# TOP.net
KiCad netlist of a schematic drawn in Altium Designer
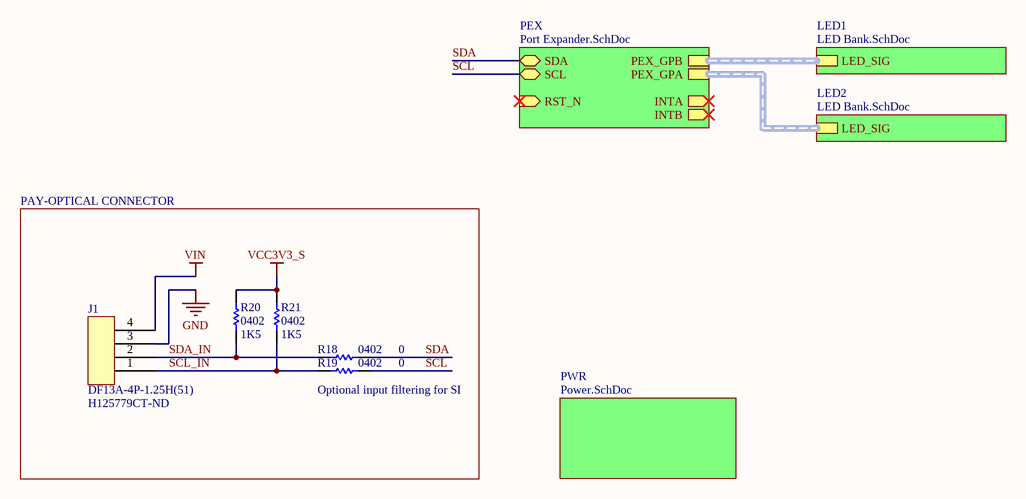
[diagram p0: TOP.SchDoc]

(export (version "E")
  (design (tool "Eeschema 10.0.6"))
  (components
    (comp (ref "J1")
      (value "DF13A-4P-1.25H(51)")
      (footprint "DF13A-4P-1.25H(51)")
      (description "4 pos DF13 right angle surface mount connector")
      (fields (field (name "SUPPLIER PART NUMBER 1") "H125779CT-ND"))
      (libsource (lib "heron-general") (part "DF13A-4P-1.25H(51)"))
    )
    (comp (ref "R18")
      (value "0402")
      (footprint "RES0402R")
      (description "0402 resistor")
      (fields
        (field (name "ALTIUM_VALUE") "0")
        (field (name "MANUFACTURER") "Panasonic")
        (field (name "MANUFACTURER PART NUMBER") "ERJ-2GE0R00X")
      )
      (libsource (lib "heron-general") (part "RES0402"))
    )
    (comp (ref "R19")
      (value "0402")
      (footprint "RES0402R")
      (description "0402 resistor")
      (fields
        (field (name "ALTIUM_VALUE") "0")
        (field (name "MANUFACTURER") "Panasonic")
        (field (name "MANUFACTURER PART NUMBER") "ERJ-2GE0R00X")
      )
      (libsource (lib "heron-general") (part "RES0402"))
    )
    (comp (ref "R20")
      (value "0402")
      (footprint "RES0402R")
      (description "0402 resistor")
      (fields (field (name "ALTIUM_VALUE") "1K5"))
      (libsource (lib "heron-general") (part "RES0402"))
    )
    (comp (ref "R21")
      (value "0402")
      (footprint "RES0402R")
      (description "0402 resistor")
      (fields (field (name "ALTIUM_VALUE") "1K5"))
      (libsource (lib "heron-general") (part "RES0402"))
    )
  )
  (nets
    (net (code "6") (name "/SCL") (class "Default")
      (node (ref "R19") (pin "2") (pinfunction "2_2") (pintype "passive"))
    )
    (net (code "7") (name "/SCL_IN") (class "Default")
      (node (ref "J1") (pin "1") (pintype "passive"))
      (node (ref "R19") (pin "1") (pinfunction "1_1") (pintype "passive"))
      (node (ref "R21") (pin "1") (pinfunction "1_1") (pintype "passive"))
    )
    (net (code "8") (name "/SDA") (class "Default")
      (node (ref "R18") (pin "2") (pinfunction "2_2") (pintype "passive"))
    )
    (net (code "9") (name "/SDA_IN") (class "Default")
      (node (ref "J1") (pin "2") (pintype "passive"))
      (node (ref "R18") (pin "1") (pinfunction "1_1") (pintype "passive"))
      (node (ref "R20") (pin "1") (pinfunction "1_1") (pintype "passive"))
    )
    (net (code "10") (name "GND") (class "Default") (node (ref "J1") (pin "3") (pintype "passive")))
    (net (code "11") (name "VCC3V3_S") (class "Default")
      (node (ref "R20") (pin "2") (pinfunction "2_2") (pintype "passive"))
      (node (ref "R21") (pin "2") (pinfunction "2_2") (pintype "passive"))
    )
    (net (code "12") (name "VIN") (class "Default") (node (ref "J1") (pin "4") (pintype "passive")))
  )
)
